# t_eau.net
KiCad netlist of a schematic drawn in EAGLE
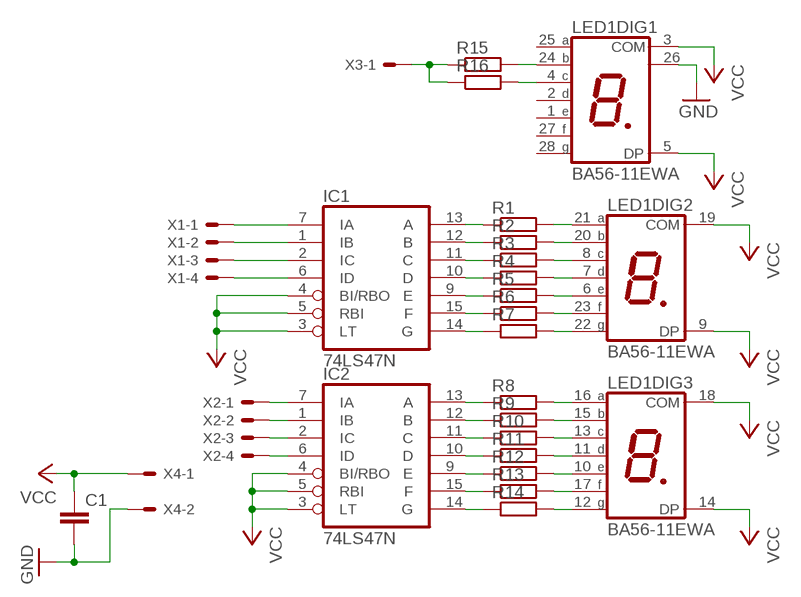
[diagram p0: schematic, sheet 1]

(export (version "E")
  (design (tool "Eeschema 10.0.6"))
  (components
    (comp (ref "C1")
      (value "C-EU025-025X050")
      (footprint "eagle-import:C025-025X050")
      (libsource (lib "eagle-import") (part "C-EU025-025X050"))
    )
    (comp (ref "IC1")
      (value "74LS47N")
      (footprint "eagle-import:DIL16")
      (libsource (lib "eagle-import") (part "7447NLS"))
    )
    (comp (ref "IC2")
      (value "74LS47N")
      (footprint "eagle-import:DIL16")
      (libsource (lib "eagle-import") (part "7447NLS"))
    )
    (comp (ref "LED1")
      (value "BA56-11EWA")
      (footprint "eagle-import:BA_BC56")
      (libsource (lib "eagle-import") (part "B?56-11WAAE"))
    )
    (comp (ref "R1")
      (value "R-EU_0204/7")
      (footprint "eagle-import:0204_7")
      (libsource (lib "eagle-import") (part "R-EU_0204/7"))
    )
    (comp (ref "R2")
      (value "R-EU_0204/7")
      (footprint "eagle-import:0204_7")
      (libsource (lib "eagle-import") (part "R-EU_0204/7"))
    )
    (comp (ref "R3")
      (value "R-EU_0204/7")
      (footprint "eagle-import:0204_7")
      (libsource (lib "eagle-import") (part "R-EU_0204/7"))
    )
    (comp (ref "R4")
      (value "R-EU_0204/7")
      (footprint "eagle-import:0204_7")
      (libsource (lib "eagle-import") (part "R-EU_0204/7"))
    )
    (comp (ref "R5")
      (value "R-EU_0204/7")
      (footprint "eagle-import:0204_7")
      (libsource (lib "eagle-import") (part "R-EU_0204/7"))
    )
    (comp (ref "R6")
      (value "R-EU_0204/7")
      (footprint "eagle-import:0204_7")
      (libsource (lib "eagle-import") (part "R-EU_0204/7"))
    )
    (comp (ref "R7")
      (value "R-EU_0204/7")
      (footprint "eagle-import:0204_7")
      (libsource (lib "eagle-import") (part "R-EU_0204/7"))
    )
    (comp (ref "R8")
      (value "R-EU_0204/7")
      (footprint "eagle-import:0204_7")
      (libsource (lib "eagle-import") (part "R-EU_0204/7"))
    )
    (comp (ref "R9")
      (value "R-EU_0204/7")
      (footprint "eagle-import:0204_7")
      (libsource (lib "eagle-import") (part "R-EU_0204/7"))
    )
    (comp (ref "R10")
      (value "R-EU_0204/7")
      (footprint "eagle-import:0204_7")
      (libsource (lib "eagle-import") (part "R-EU_0204/7"))
    )
    (comp (ref "R11")
      (value "R-EU_0204/7")
      (footprint "eagle-import:0204_7")
      (libsource (lib "eagle-import") (part "R-EU_0204/7"))
    )
    (comp (ref "R12")
      (value "R-EU_0204/7")
      (footprint "eagle-import:0204_7")
      (libsource (lib "eagle-import") (part "R-EU_0204/7"))
    )
    (comp (ref "R13")
      (value "R-EU_0204/7")
      (footprint "eagle-import:0204_7")
      (libsource (lib "eagle-import") (part "R-EU_0204/7"))
    )
    (comp (ref "R14")
      (value "R-EU_0204/7")
      (footprint "eagle-import:0204_7")
      (libsource (lib "eagle-import") (part "R-EU_0204/7"))
    )
    (comp (ref "R15")
      (value "R-EU_0204/7")
      (footprint "eagle-import:0204_7")
      (libsource (lib "eagle-import") (part "R-EU_0204/7"))
    )
    (comp (ref "R16")
      (value "R-EU_0204/7")
      (footprint "eagle-import:0204_7")
      (libsource (lib "eagle-import") (part "R-EU_0204/7"))
    )
    (comp (ref "X1")
      (value "KK-156-7")
      (footprint "eagle-import:KK-156-7")
      (libsource (lib "eagle-import") (part "KK-156-7"))
    )
    (comp (ref "X2")
      (value "KK-156-7")
      (footprint "eagle-import:KK-156-7")
      (libsource (lib "eagle-import") (part "KK-156-7"))
    )
    (comp (ref "X3")
      (value "KK-156-2")
      (footprint "eagle-import:KK-156-2")
      (libsource (lib "eagle-import") (part "KK-156-2"))
    )
    (comp (ref "X4")
      (value "KK-156-2")
      (footprint "eagle-import:KK-156-2")
      (libsource (lib "eagle-import") (part "KK-156-2"))
    )
  )
  (nets
    (net (code "1") (name "GND") (class "Default")
      (node (ref "C1") (pin "2") (pinfunction "2_2") (pintype "passive"))
      (node (ref "LED1") (pin "26") (pinfunction "COM_26") (pintype "passive"))
      (node (ref "X4") (pin "2") (pinfunction "S_2") (pintype "passive"))
    )
    (net (code "2") (name "Net-(IC1A-A)") (class "Default")
      (node (ref "IC1") (pin "13") (pinfunction "A_13") (pintype "output"))
      (node (ref "R1") (pin "1") (pinfunction "1_1") (pintype "passive"))
    )
    (net (code "3") (name "Net-(IC1A-B)") (class "Default")
      (node (ref "IC1") (pin "12") (pinfunction "B_12") (pintype "output"))
      (node (ref "R2") (pin "1") (pinfunction "1_1") (pintype "passive"))
    )
    (net (code "4") (name "Net-(IC1A-C)") (class "Default")
      (node (ref "IC1") (pin "11") (pinfunction "C_11") (pintype "output"))
      (node (ref "R3") (pin "1") (pinfunction "1_1") (pintype "passive"))
    )
    (net (code "5") (name "Net-(IC1A-D)") (class "Default")
      (node (ref "IC1") (pin "10") (pinfunction "D_10") (pintype "output"))
      (node (ref "R4") (pin "1") (pinfunction "1_1") (pintype "passive"))
    )
    (net (code "6") (name "Net-(IC1A-E)") (class "Default")
      (node (ref "IC1") (pin "9") (pinfunction "E_9") (pintype "output"))
      (node (ref "R5") (pin "1") (pinfunction "1_1") (pintype "passive"))
    )
    (net (code "7") (name "Net-(IC1A-F)") (class "Default")
      (node (ref "IC1") (pin "15") (pinfunction "F_15") (pintype "output"))
      (node (ref "R6") (pin "1") (pinfunction "1_1") (pintype "passive"))
    )
    (net (code "8") (name "Net-(IC1A-G)") (class "Default")
      (node (ref "IC1") (pin "14") (pinfunction "G_14") (pintype "output"))
      (node (ref "R7") (pin "1") (pinfunction "1_1") (pintype "passive"))
    )
    (net (code "9") (name "Net-(IC1A-IA)") (class "Default")
      (node (ref "IC1") (pin "7") (pinfunction "IA_7") (pintype "input"))
      (node (ref "X1") (pin "1") (pinfunction "S_1") (pintype "passive"))
    )
    (net (code "10") (name "Net-(IC1A-IB)") (class "Default")
      (node (ref "IC1") (pin "1") (pinfunction "IB_1") (pintype "input"))
      (node (ref "X1") (pin "2") (pinfunction "S_2") (pintype "passive"))
    )
    (net (code "11") (name "Net-(IC1A-IC)") (class "Default")
      (node (ref "IC1") (pin "2") (pinfunction "IC_2") (pintype "input"))
      (node (ref "X1") (pin "3") (pinfunction "S_3") (pintype "passive"))
    )
    (net (code "12") (name "Net-(IC1A-ID)") (class "Default")
      (node (ref "IC1") (pin "6") (pinfunction "ID_6") (pintype "input"))
      (node (ref "X1") (pin "4") (pinfunction "S_4") (pintype "passive"))
    )
    (net (code "13") (name "Net-(IC2A-A)") (class "Default")
      (node (ref "IC2") (pin "13") (pinfunction "A_13") (pintype "output"))
      (node (ref "R8") (pin "1") (pinfunction "1_1") (pintype "passive"))
    )
    (net (code "14") (name "Net-(IC2A-B)") (class "Default")
      (node (ref "IC2") (pin "12") (pinfunction "B_12") (pintype "output"))
      (node (ref "R9") (pin "1") (pinfunction "1_1") (pintype "passive"))
    )
    (net (code "15") (name "Net-(IC2A-C)") (class "Default")
      (node (ref "IC2") (pin "11") (pinfunction "C_11") (pintype "output"))
      (node (ref "R10") (pin "1") (pinfunction "1_1") (pintype "passive"))
    )
    (net (code "16") (name "Net-(IC2A-D)") (class "Default")
      (node (ref "IC2") (pin "10") (pinfunction "D_10") (pintype "output"))
      (node (ref "R11") (pin "1") (pinfunction "1_1") (pintype "passive"))
    )
    (net (code "17") (name "Net-(IC2A-E)") (class "Default")
      (node (ref "IC2") (pin "9") (pinfunction "E_9") (pintype "output"))
      (node (ref "R12") (pin "1") (pinfunction "1_1") (pintype "passive"))
    )
    (net (code "18") (name "Net-(IC2A-F)") (class "Default")
      (node (ref "IC2") (pin "15") (pinfunction "F_15") (pintype "output"))
      (node (ref "R13") (pin "1") (pinfunction "1_1") (pintype "passive"))
    )
    (net (code "19") (name "Net-(IC2A-G)") (class "Default")
      (node (ref "IC2") (pin "14") (pinfunction "G_14") (pintype "output"))
      (node (ref "R14") (pin "1") (pinfunction "1_1") (pintype "passive"))
    )
    (net (code "20") (name "Net-(IC2A-IA)") (class "Default")
      (node (ref "IC2") (pin "7") (pinfunction "IA_7") (pintype "input"))
      (node (ref "X2") (pin "1") (pinfunction "S_1") (pintype "passive"))
    )
    (net (code "21") (name "Net-(IC2A-IB)") (class "Default")
      (node (ref "IC2") (pin "1") (pinfunction "IB_1") (pintype "input"))
      (node (ref "X2") (pin "2") (pinfunction "S_2") (pintype "passive"))
    )
    (net (code "22") (name "Net-(IC2A-IC)") (class "Default")
      (node (ref "IC2") (pin "2") (pinfunction "IC_2") (pintype "input"))
      (node (ref "X2") (pin "3") (pinfunction "S_3") (pintype "passive"))
    )
    (net (code "23") (name "Net-(IC2A-ID)") (class "Default")
      (node (ref "IC2") (pin "6") (pinfunction "ID_6") (pintype "input"))
      (node (ref "X2") (pin "4") (pinfunction "S_4") (pintype "passive"))
    )
    (net (code "24") (name "Net-(LED1A-B)") (class "Default")
      (node (ref "LED1") (pin "24") (pinfunction "B_24") (pintype "passive"))
      (node (ref "R15") (pin "2") (pinfunction "2_2") (pintype "passive"))
    )
    (net (code "25") (name "Net-(LED1A-C)") (class "Default")
      (node (ref "LED1") (pin "4") (pinfunction "C_4") (pintype "passive"))
      (node (ref "R16") (pin "2") (pinfunction "2_2") (pintype "passive"))
    )
    (net (code "26") (name "Net-(LED1B-A)") (class "Default")
      (node (ref "LED1") (pin "21") (pinfunction "A_21") (pintype "passive"))
      (node (ref "R1") (pin "2") (pinfunction "2_2") (pintype "passive"))
    )
    (net (code "27") (name "Net-(LED1B-B)") (class "Default")
      (node (ref "LED1") (pin "20") (pinfunction "B_20") (pintype "passive"))
      (node (ref "R2") (pin "2") (pinfunction "2_2") (pintype "passive"))
    )
    (net (code "28") (name "Net-(LED1B-C)") (class "Default")
      (node (ref "LED1") (pin "8") (pinfunction "C_8") (pintype "passive"))
      (node (ref "R3") (pin "2") (pinfunction "2_2") (pintype "passive"))
    )
    (net (code "29") (name "Net-(LED1B-D)") (class "Default")
      (node (ref "LED1") (pin "7") (pinfunction "D_7") (pintype "passive"))
      (node (ref "R4") (pin "2") (pinfunction "2_2") (pintype "passive"))
    )
    (net (code "30") (name "Net-(LED1B-E)") (class "Default")
      (node (ref "LED1") (pin "6") (pinfunction "E_6") (pintype "passive"))
      (node (ref "R5") (pin "2") (pinfunction "2_2") (pintype "passive"))
    )
    (net (code "31") (name "Net-(LED1B-F)") (class "Default")
      (node (ref "LED1") (pin "23") (pinfunction "F_23") (pintype "passive"))
      (node (ref "R6") (pin "2") (pinfunction "2_2") (pintype "passive"))
    )
    (net (code "32") (name "Net-(LED1B-G)") (class "Default")
      (node (ref "LED1") (pin "22") (pinfunction "G_22") (pintype "passive"))
      (node (ref "R7") (pin "2") (pinfunction "2_2") (pintype "passive"))
    )
    (net (code "33") (name "Net-(LED1C-A)") (class "Default")
      (node (ref "LED1") (pin "16") (pinfunction "A_16") (pintype "passive"))
      (node (ref "R8") (pin "2") (pinfunction "2_2") (pintype "passive"))
    )
    (net (code "34") (name "Net-(LED1C-B)") (class "Default")
      (node (ref "LED1") (pin "15") (pinfunction "B_15") (pintype "passive"))
      (node (ref "R9") (pin "2") (pinfunction "2_2") (pintype "passive"))
    )
    (net (code "35") (name "Net-(LED1C-C)") (class "Default")
      (node (ref "LED1") (pin "13") (pinfunction "C_13") (pintype "passive"))
      (node (ref "R10") (pin "2") (pinfunction "2_2") (pintype "passive"))
    )
    (net (code "36") (name "Net-(LED1C-D)") (class "Default")
      (node (ref "LED1") (pin "11") (pinfunction "D_11") (pintype "passive"))
      (node (ref "R11") (pin "2") (pinfunction "2_2") (pintype "passive"))
    )
    (net (code "37") (name "Net-(LED1C-E)") (class "Default")
      (node (ref "LED1") (pin "10") (pinfunction "E_10") (pintype "passive"))
      (node (ref "R12") (pin "2") (pinfunction "2_2") (pintype "passive"))
    )
    (net (code "38") (name "Net-(LED1C-F)") (class "Default")
      (node (ref "LED1") (pin "17") (pinfunction "F_17") (pintype "passive"))
      (node (ref "R13") (pin "2") (pinfunction "2_2") (pintype "passive"))
    )
    (net (code "39") (name "Net-(LED1C-G)") (class "Default")
      (node (ref "LED1") (pin "12") (pinfunction "G_12") (pintype "passive"))
      (node (ref "R14") (pin "2") (pinfunction "2_2") (pintype "passive"))
    )
    (net (code "40") (name "Net-(X3A-S)") (class "Default")
      (node (ref "R15") (pin "1") (pinfunction "1_1") (pintype "passive"))
      (node (ref "R16") (pin "1") (pinfunction "1_1") (pintype "passive"))
      (node (ref "X3") (pin "1") (pinfunction "S_1") (pintype "passive"))
    )
    (net (code "41") (name "VCC") (class "Default")
      (node (ref "C1") (pin "1") (pinfunction "1_1") (pintype "passive"))
      (node (ref "IC1") (pin "3") (pinfunction "LT_3") (pintype "input"))
      (node (ref "IC1") (pin "4") (pinfunction "BI/RBO_4") (pintype "input"))
      (node (ref "IC1") (pin "5") (pinfunction "RBI_5") (pintype "input"))
      (node (ref "IC2") (pin "3") (pinfunction "LT_3") (pintype "input"))
      (node (ref "IC2") (pin "4") (pinfunction "BI/RBO_4") (pintype "input"))
      (node (ref "IC2") (pin "5") (pinfunction "RBI_5") (pintype "input"))
      (node (ref "LED1") (pin "14") (pinfunction "DP_14") (pintype "passive"))
      (node (ref "LED1") (pin "18") (pinfunction "COM_18") (pintype "passive"))
      (node (ref "LED1") (pin "19") (pinfunction "COM_19") (pintype "passive"))
      (node (ref "LED1") (pin "3") (pinfunction "COM_3") (pintype "passive"))
      (node (ref "LED1") (pin "5") (pinfunction "DP_5") (pintype "passive"))
      (node (ref "LED1") (pin "9") (pinfunction "DP_9") (pintype "passive"))
      (node (ref "X4") (pin "1") (pinfunction "S_1") (pintype "passive"))
    )
    (net (code "42") (name "unconnected-(LED1A-A-Pad25)") (class "Default")
      (node (ref "LED1") (pin "25") (pinfunction "A_25") (pintype "passive"))
    )
    (net (code "43") (name "unconnected-(LED1A-D-Pad2)") (class "Default")
      (node (ref "LED1") (pin "2") (pinfunction "D_2") (pintype "passive"))
    )
    (net (code "44") (name "unconnected-(LED1A-E-Pad1)") (class "Default")
      (node (ref "LED1") (pin "1") (pinfunction "E_1") (pintype "passive"))
    )
    (net (code "45") (name "unconnected-(LED1A-F-Pad27)") (class "Default")
      (node (ref "LED1") (pin "27") (pinfunction "F_27") (pintype "passive"))
    )
    (net (code "46") (name "unconnected-(LED1A-G-Pad28)") (class "Default")
      (node (ref "LED1") (pin "28") (pinfunction "G_28") (pintype "passive"))
    )
  )
)
